# 2_LDO_5V.net
KiCad netlist of a schematic drawn in Altium Designer
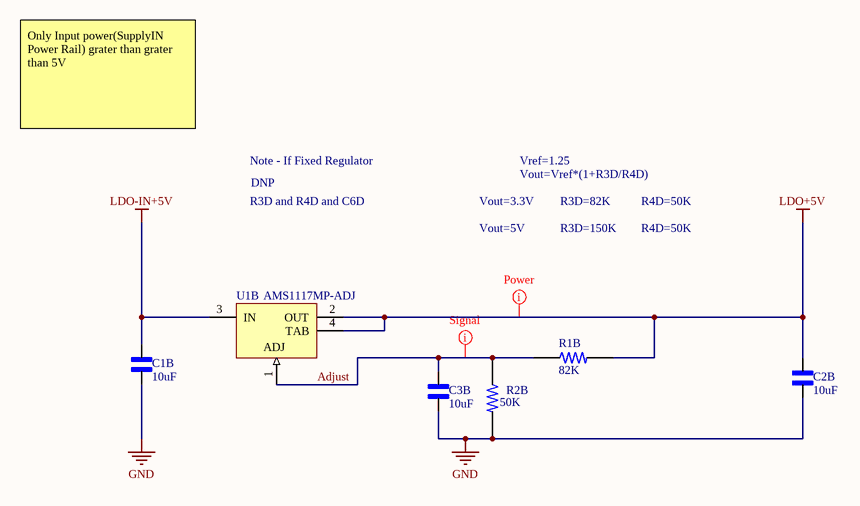
[diagram p0: 2_LDO+5V.SchDoc]

(export (version "E")
  (design (tool "Eeschema 10.0.6"))
  (components
    (comp (ref "C1B")
      (value "10uF")
      (footprint "C-0603")
      (description "Ceramic Capacitor 16V 0603 (1608 Metric)")
      (fields (field (name "MP") "C0603C104J4RAC") (field (name "MF") "KEMET"))
      (libsource (lib "ESP-12F_WLED_IOT_LIPO") (part "C-0603"))
    )
    (comp (ref "C2B")
      (value "10uF")
      (footprint "C-0603")
      (description "Ceramic Capacitor 16V 0603 (1608 Metric)")
      (fields (field (name "MP") "C0603C104J4RAC") (field (name "MF") "KEMET"))
      (libsource (lib "ESP-12F_WLED_IOT_LIPO") (part "C-0603"))
    )
    (comp (ref "C3B")
      (value "10uF")
      (footprint "C-0603")
      (description "Ceramic Capacitor 16V 0603 (1608 Metric)")
      (fields (field (name "MP") "C0603C104J4RAC") (field (name "MF") "KEMET"))
      (libsource (lib "ESP-12F_WLED_IOT_LIPO") (part "C-0603"))
    )
    (comp (ref "R1B")
      (value "82K")
      (footprint "R-0603")
      (description "0603")
      (fields (field (name "MP") "2-1623703-0") (field (name "TOLERANCE") "1%"))
      (libsource (lib "ESP-12F_WLED_IOT_LIPO") (part "R-0603"))
    )
    (comp (ref "R2B")
      (value "50K")
      (footprint "R-0603")
      (description "0603")
      (fields (field (name "MP") "2-1623703-0") (field (name "TOLERANCE") "1%"))
      (libsource (lib "ESP-12F_WLED_IOT_LIPO") (part "R-0603"))
    )
    (comp (ref "U1B")
      (value "AMS1117MP-ADJ")
      (footprint "MP04A_N")
      (description "800mA Low-Dropout Linear Regulator, 4-pin SOT-223")
      (fields
        (field (name "PARTNUMBER") "LM1117MP-ADJ")
        (field (name "MANUFACTURER") "National Semiconductor")
      )
      (libsource (lib "ESP-12F_WLED_IOT_LIPO") (part "PM-REG-LM1086ADJ-SOT4"))
    )
  )
  (nets
    (net (code "1") (name "/Adjust") (class "Default")
      (node (ref "C3B") (pin "2") (pinfunction "2_2") (pintype "passive"))
      (node (ref "R1B") (pin "1") (pinfunction "1_1") (pintype "passive"))
      (node (ref "R2B") (pin "1") (pinfunction "1_1") (pintype "passive"))
      (node (ref "U1B") (pin "1") (pinfunction "ADJ_1") (pintype "input"))
    )
    (net (code "2") (name "GND") (class "Default")
      (node (ref "C1B") (pin "1") (pinfunction "1_1") (pintype "passive"))
      (node (ref "C2B") (pin "1") (pinfunction "1_1") (pintype "passive"))
      (node (ref "C3B") (pin "1") (pinfunction "1_1") (pintype "passive"))
      (node (ref "R2B") (pin "2") (pinfunction "2_2") (pintype "passive"))
    )
    (net (code "3") (name "LDO+5V") (class "Default")
      (node (ref "C2B") (pin "2") (pinfunction "2_2") (pintype "passive"))
      (node (ref "R1B") (pin "2") (pinfunction "2_2") (pintype "passive"))
      (node (ref "U1B") (pin "2") (pinfunction "OUT_2") (pintype "power_in"))
      (node (ref "U1B") (pin "4") (pinfunction "TAB_4") (pintype "power_in"))
    )
    (net (code "4") (name "LDO-IN+5V") (class "Default")
      (node (ref "C1B") (pin "2") (pinfunction "2_2") (pintype "passive"))
      (node (ref "U1B") (pin "3") (pinfunction "IN_3") (pintype "power_in"))
    )
  )
)
